# LoopSup.net
KiCad netlist of a schematic drawn in EAGLE
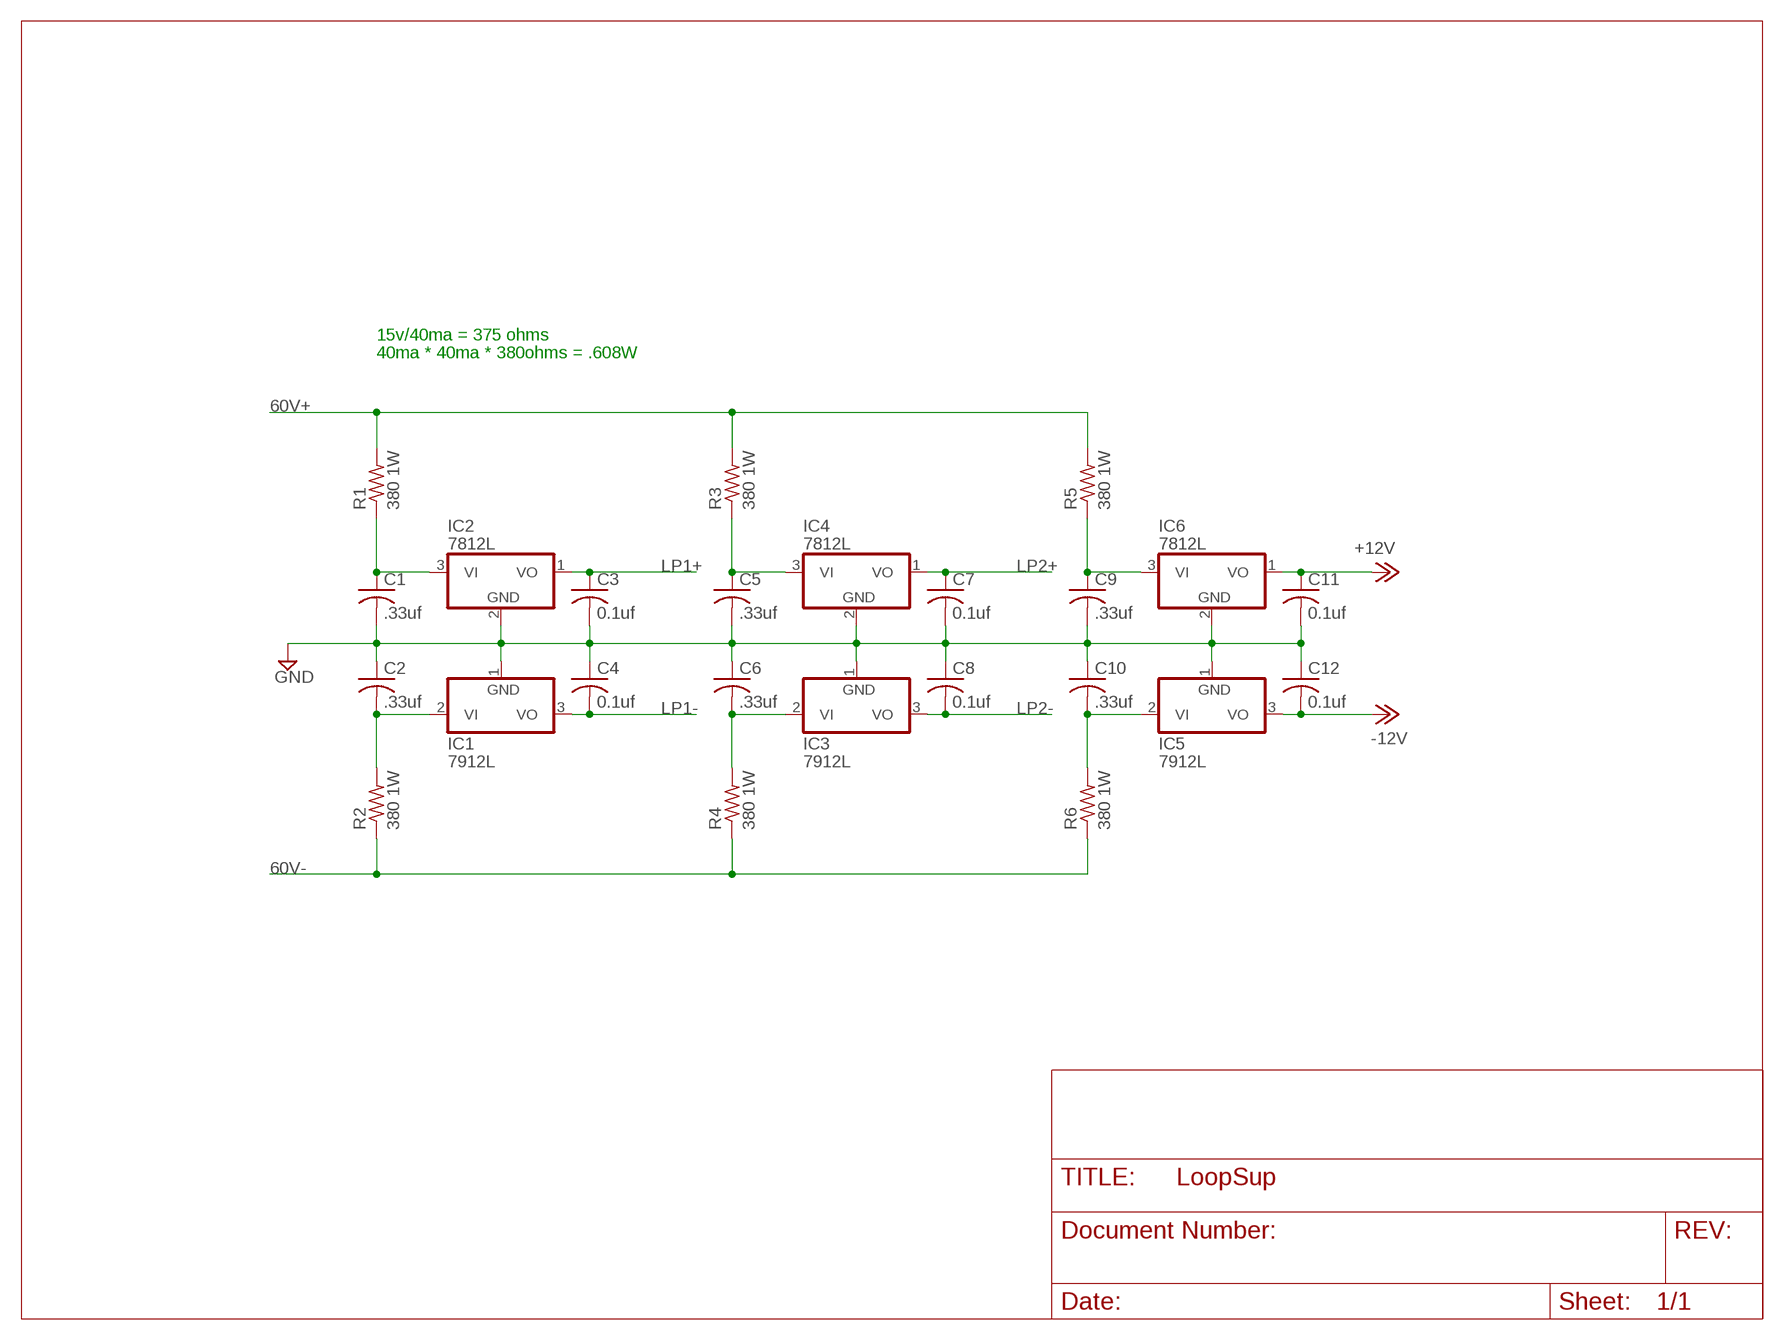
[diagram p0: schematic, sheet 1]

(export (version "E")
  (design (tool "Eeschema 10.0.6"))
  (components
    (comp (ref "C1")
      (value ".33uf")
      (footprint "eagle-import:C050-025X075")
      (libsource (lib "eagle-import") (part "C-US050-025X075"))
    )
    (comp (ref "C2")
      (value ".33uf")
      (footprint "eagle-import:C050-025X075")
      (libsource (lib "eagle-import") (part "C-US050-025X075"))
    )
    (comp (ref "C3")
      (value "0.1uf")
      (footprint "eagle-import:C050-025X075")
      (libsource (lib "eagle-import") (part "C-US050-025X075"))
    )
    (comp (ref "C4")
      (value "0.1uf")
      (footprint "eagle-import:C050-025X075")
      (libsource (lib "eagle-import") (part "C-US050-025X075"))
    )
    (comp (ref "C5")
      (value ".33uf")
      (footprint "eagle-import:C050-025X075")
      (libsource (lib "eagle-import") (part "C-US050-025X075"))
    )
    (comp (ref "C6")
      (value ".33uf")
      (footprint "eagle-import:C050-025X075")
      (libsource (lib "eagle-import") (part "C-US050-025X075"))
    )
    (comp (ref "C7")
      (value "0.1uf")
      (footprint "eagle-import:C050-025X075")
      (libsource (lib "eagle-import") (part "C-US050-025X075"))
    )
    (comp (ref "C8")
      (value "0.1uf")
      (footprint "eagle-import:C050-025X075")
      (libsource (lib "eagle-import") (part "C-US050-025X075"))
    )
    (comp (ref "C9")
      (value ".33uf")
      (footprint "eagle-import:C050-025X075")
      (libsource (lib "eagle-import") (part "C-US050-025X075"))
    )
    (comp (ref "C10")
      (value ".33uf")
      (footprint "eagle-import:C050-025X075")
      (libsource (lib "eagle-import") (part "C-US050-025X075"))
    )
    (comp (ref "C11")
      (value "0.1uf")
      (footprint "eagle-import:C050-025X075")
      (libsource (lib "eagle-import") (part "C-US050-025X075"))
    )
    (comp (ref "C12")
      (value "0.1uf")
      (footprint "eagle-import:C050-025X075")
      (libsource (lib "eagle-import") (part "C-US050-025X075"))
    )
    (comp (ref "IC1")
      (value "7912L")
      (footprint "eagle-import:TO92")
      (libsource (lib "eagle-import") (part "79L12"))
    )
    (comp (ref "IC2")
      (value "7812L")
      (footprint "eagle-import:TO92")
      (libsource (lib "eagle-import") (part "78L12"))
    )
    (comp (ref "IC3")
      (value "7912L")
      (footprint "eagle-import:TO92")
      (libsource (lib "eagle-import") (part "79L12"))
    )
    (comp (ref "IC4")
      (value "7812L")
      (footprint "eagle-import:TO92")
      (libsource (lib "eagle-import") (part "78L12"))
    )
    (comp (ref "IC5")
      (value "7912L")
      (footprint "eagle-import:TO92")
      (libsource (lib "eagle-import") (part "79L12"))
    )
    (comp (ref "IC6")
      (value "7812L")
      (footprint "eagle-import:TO92")
      (libsource (lib "eagle-import") (part "78L12"))
    )
    (comp (ref "R1")
      (value "380 1W")
      (footprint "eagle-import:0309_12")
      (libsource (lib "eagle-import") (part "R-US_0309/12"))
    )
    (comp (ref "R2")
      (value "380 1W")
      (footprint "eagle-import:0309_12")
      (libsource (lib "eagle-import") (part "R-US_0309/12"))
    )
    (comp (ref "R3")
      (value "380 1W")
      (footprint "eagle-import:0309_12")
      (libsource (lib "eagle-import") (part "R-US_0309/12"))
    )
    (comp (ref "R4")
      (value "380 1W")
      (footprint "eagle-import:0309_12")
      (libsource (lib "eagle-import") (part "R-US_0309/12"))
    )
    (comp (ref "R5")
      (value "380 1W")
      (footprint "eagle-import:0309_12")
      (libsource (lib "eagle-import") (part "R-US_0309/12"))
    )
    (comp (ref "R6")
      (value "380 1W")
      (footprint "eagle-import:0309_12")
      (libsource (lib "eagle-import") (part "R-US_0309/12"))
    )
  )
  (nets
    (net (code "1") (name "+12V") (class "Default")
      (node (ref "C11") (pin "1") (pinfunction "1_1") (pintype "passive"))
      (node (ref "IC6") (pin "1") (pinfunction "VO_1") (pintype "passive"))
    )
    (net (code "2") (name "-12V") (class "Default")
      (node (ref "C12") (pin "2") (pinfunction "2_2") (pintype "passive"))
      (node (ref "IC5") (pin "3") (pinfunction "VO_3") (pintype "passive"))
    )
    (net (code "3") (name "/60V+") (class "Default")
      (node (ref "R1") (pin "2") (pinfunction "2_2") (pintype "passive"))
      (node (ref "R3") (pin "2") (pinfunction "2_2") (pintype "passive"))
      (node (ref "R5") (pin "2") (pinfunction "2_2") (pintype "passive"))
    )
    (net (code "4") (name "/60V-") (class "Default")
      (node (ref "R2") (pin "1") (pinfunction "1_1") (pintype "passive"))
      (node (ref "R4") (pin "1") (pinfunction "1_1") (pintype "passive"))
      (node (ref "R6") (pin "1") (pinfunction "1_1") (pintype "passive"))
    )
    (net (code "5") (name "/LP1+") (class "Default")
      (node (ref "C3") (pin "1") (pinfunction "1_1") (pintype "passive"))
      (node (ref "IC2") (pin "1") (pinfunction "VO_1") (pintype "passive"))
    )
    (net (code "6") (name "/LP1-") (class "Default")
      (node (ref "C4") (pin "2") (pinfunction "2_2") (pintype "passive"))
      (node (ref "IC1") (pin "3") (pinfunction "VO_3") (pintype "passive"))
    )
    (net (code "7") (name "/LP2+") (class "Default")
      (node (ref "C7") (pin "1") (pinfunction "1_1") (pintype "passive"))
      (node (ref "IC4") (pin "1") (pinfunction "VO_1") (pintype "passive"))
    )
    (net (code "8") (name "/LP2-") (class "Default")
      (node (ref "C8") (pin "2") (pinfunction "2_2") (pintype "passive"))
      (node (ref "IC3") (pin "3") (pinfunction "VO_3") (pintype "passive"))
    )
    (net (code "9") (name "GND") (class "Default")
      (node (ref "C1") (pin "2") (pinfunction "2_2") (pintype "passive"))
      (node (ref "C10") (pin "1") (pinfunction "1_1") (pintype "passive"))
      (node (ref "C11") (pin "2") (pinfunction "2_2") (pintype "passive"))
      (node (ref "C12") (pin "1") (pinfunction "1_1") (pintype "passive"))
      (node (ref "C2") (pin "1") (pinfunction "1_1") (pintype "passive"))
      (node (ref "C3") (pin "2") (pinfunction "2_2") (pintype "passive"))
      (node (ref "C4") (pin "1") (pinfunction "1_1") (pintype "passive"))
      (node (ref "C5") (pin "2") (pinfunction "2_2") (pintype "passive"))
      (node (ref "C6") (pin "1") (pinfunction "1_1") (pintype "passive"))
      (node (ref "C7") (pin "2") (pinfunction "2_2") (pintype "passive"))
      (node (ref "C8") (pin "1") (pinfunction "1_1") (pintype "passive"))
      (node (ref "C9") (pin "2") (pinfunction "2_2") (pintype "passive"))
      (node (ref "IC1") (pin "1") (pinfunction "GND_1") (pintype "passive"))
      (node (ref "IC2") (pin "2") (pinfunction "GND_2") (pintype "passive"))
      (node (ref "IC3") (pin "1") (pinfunction "GND_1") (pintype "passive"))
      (node (ref "IC4") (pin "2") (pinfunction "GND_2") (pintype "passive"))
      (node (ref "IC5") (pin "1") (pinfunction "GND_1") (pintype "passive"))
      (node (ref "IC6") (pin "2") (pinfunction "GND_2") (pintype "passive"))
    )
    (net (code "10") (name "Net-(IC1-VI)") (class "Default")
      (node (ref "C2") (pin "2") (pinfunction "2_2") (pintype "passive"))
      (node (ref "IC1") (pin "2") (pinfunction "VI_2") (pintype "input"))
      (node (ref "R2") (pin "2") (pinfunction "2_2") (pintype "passive"))
    )
    (net (code "11") (name "Net-(IC2-VI)") (class "Default")
      (node (ref "C1") (pin "1") (pinfunction "1_1") (pintype "passive"))
      (node (ref "IC2") (pin "3") (pinfunction "VI_3") (pintype "input"))
      (node (ref "R1") (pin "1") (pinfunction "1_1") (pintype "passive"))
    )
    (net (code "12") (name "Net-(IC3-VI)") (class "Default")
      (node (ref "C6") (pin "2") (pinfunction "2_2") (pintype "passive"))
      (node (ref "IC3") (pin "2") (pinfunction "VI_2") (pintype "input"))
      (node (ref "R4") (pin "2") (pinfunction "2_2") (pintype "passive"))
    )
    (net (code "13") (name "Net-(IC4-VI)") (class "Default")
      (node (ref "C5") (pin "1") (pinfunction "1_1") (pintype "passive"))
      (node (ref "IC4") (pin "3") (pinfunction "VI_3") (pintype "input"))
      (node (ref "R3") (pin "1") (pinfunction "1_1") (pintype "passive"))
    )
    (net (code "14") (name "Net-(IC5-VI)") (class "Default")
      (node (ref "C10") (pin "2") (pinfunction "2_2") (pintype "passive"))
      (node (ref "IC5") (pin "2") (pinfunction "VI_2") (pintype "input"))
      (node (ref "R6") (pin "2") (pinfunction "2_2") (pintype "passive"))
    )
    (net (code "15") (name "Net-(IC6-VI)") (class "Default")
      (node (ref "C9") (pin "1") (pinfunction "1_1") (pintype "passive"))
      (node (ref "IC6") (pin "3") (pinfunction "VI_3") (pintype "input"))
      (node (ref "R5") (pin "1") (pinfunction "1_1") (pintype "passive"))
    )
  )
)
